# 33_DRAM-DDR4_2x16bit_96P.net
KiCad netlist of a schematic drawn in Altium Designer
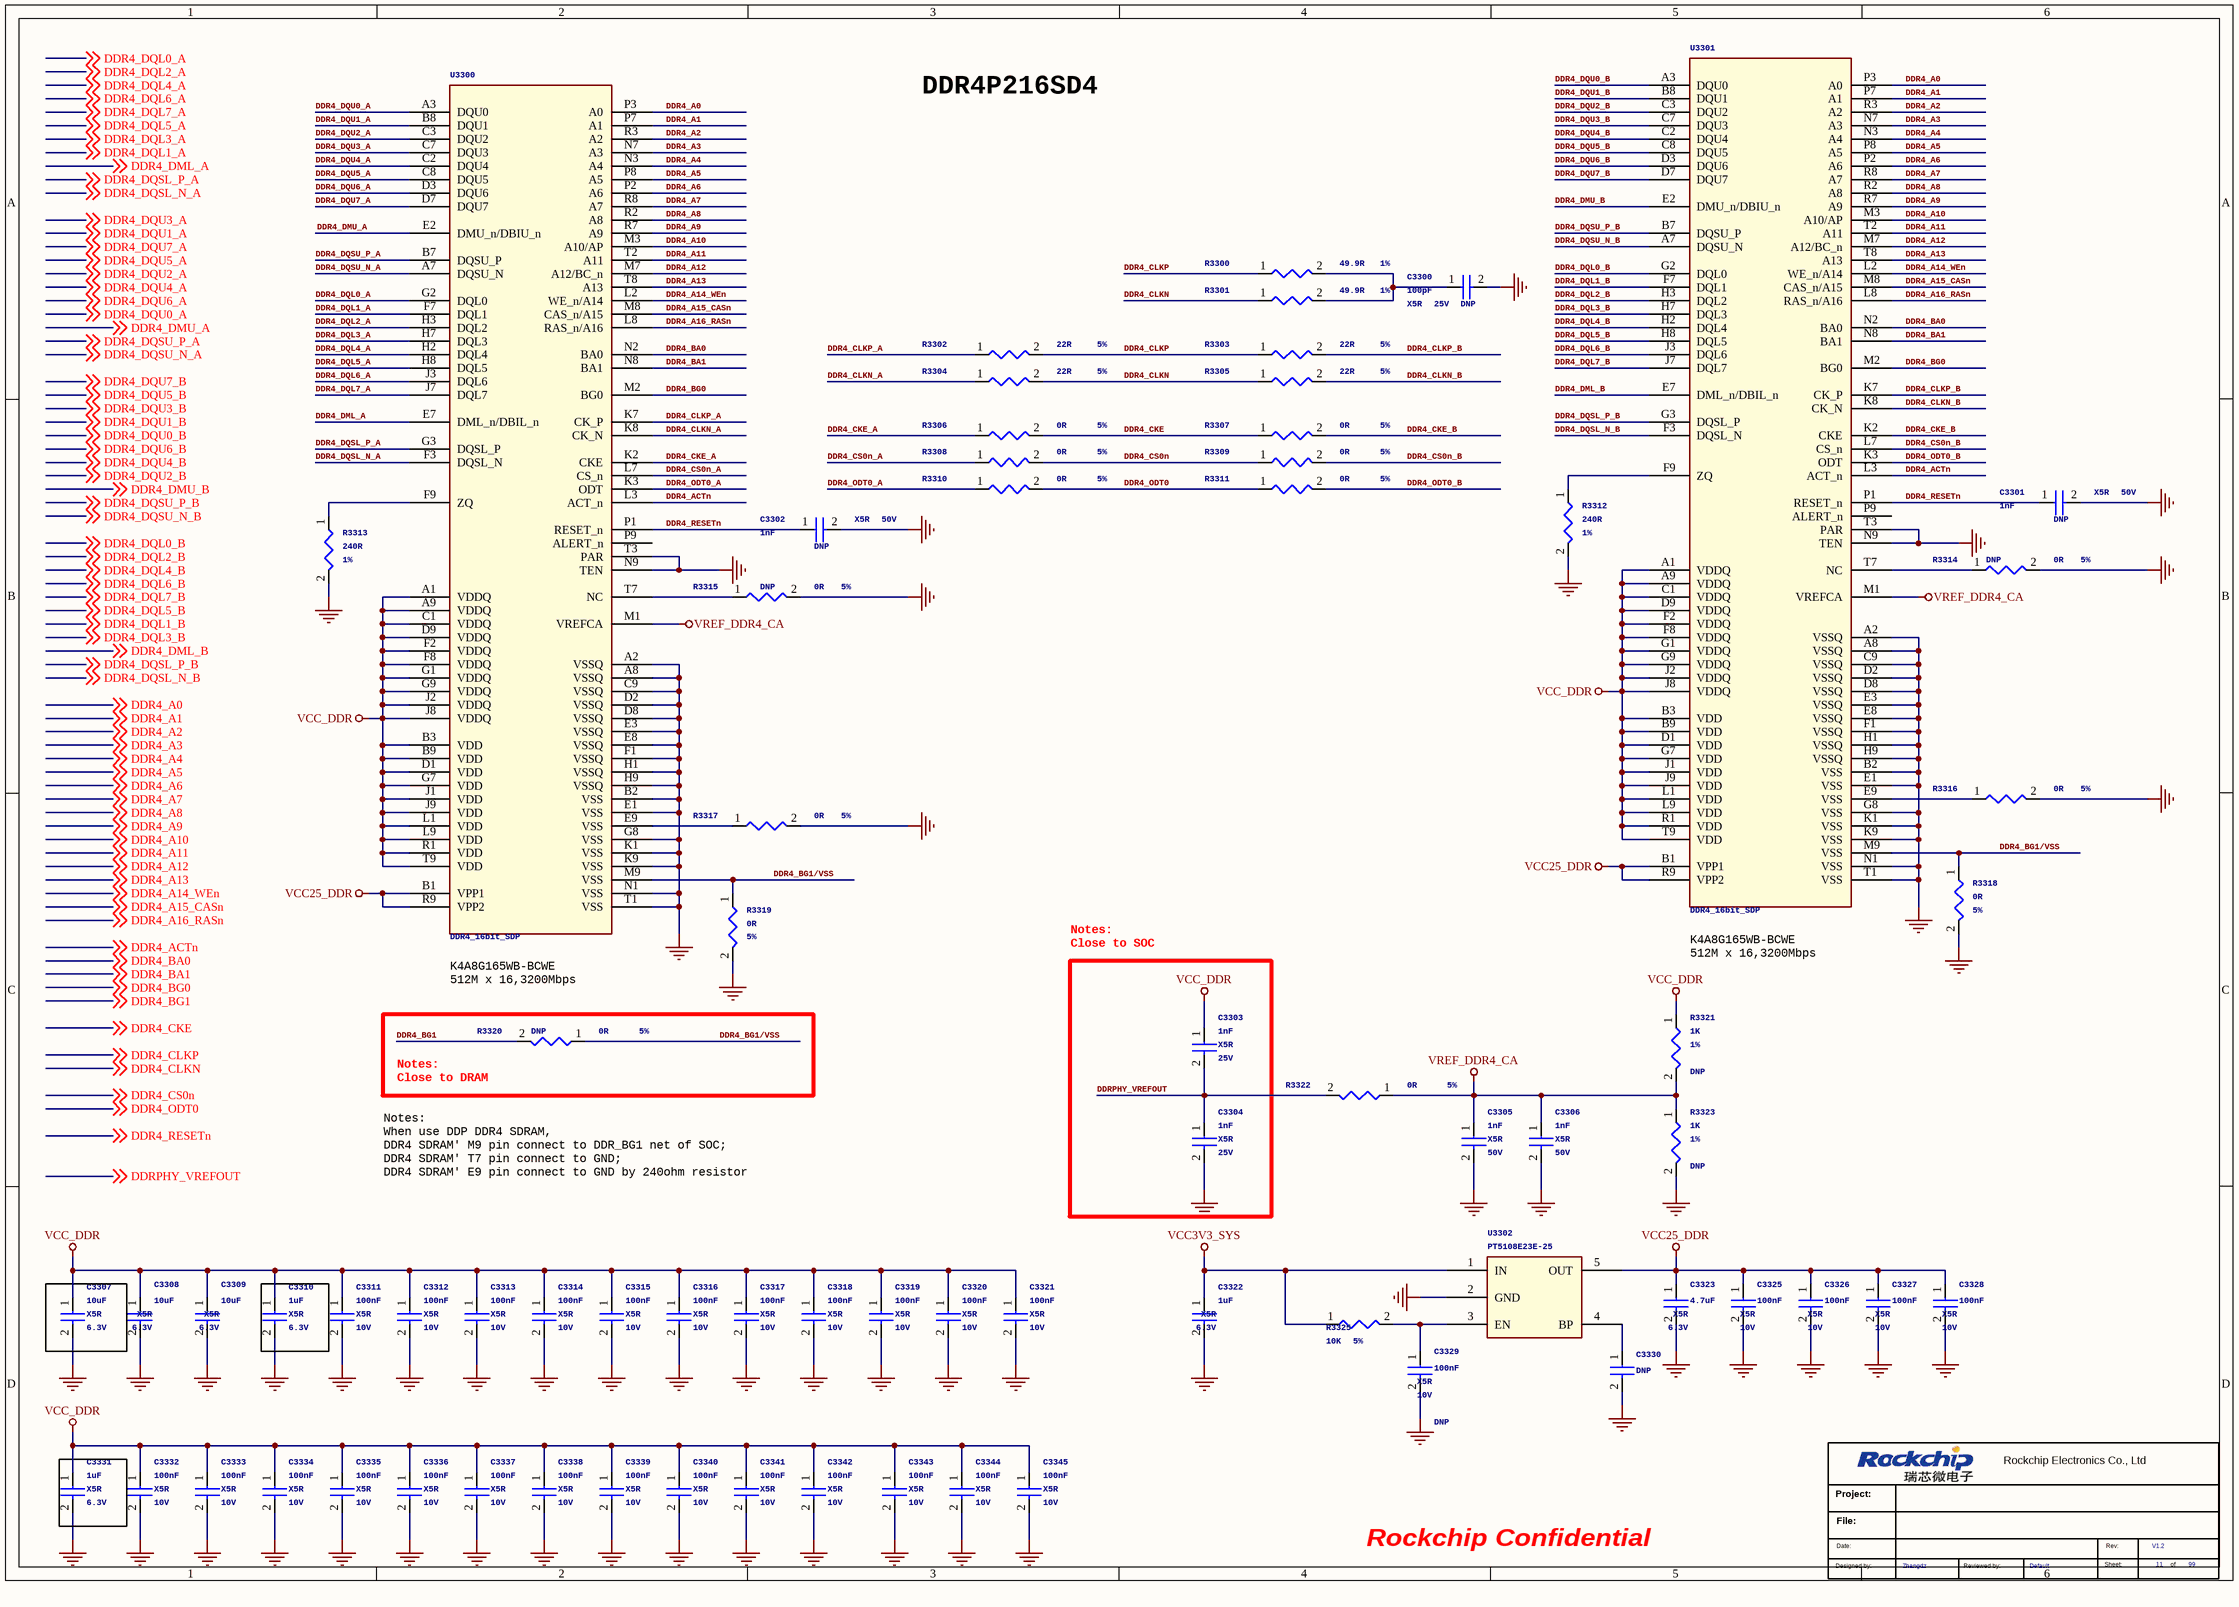
[diagram p0: 33.DRAM-DDR4_2x16bit_96P.SchDoc]

(export (version "E")
  (design (tool "Eeschema 10.0.6"))
  (components
    (comp (ref "*")
      (value "Rockchip_new")
      (fields
        (field (name "SCHEMATIC PAGE COUNT") "99")
        (field (name "SCHEMATIC PAGE NUMBER") "11")
        (field (name "DESIGNER") "Zhangdz")
        (field (name "REVISION") "V1.2")
        (field (name "CHECK") "Default")
      )
      (libsource (lib "*") (part "Rockchip_new"))
    )
    (comp (ref "C3300")
      (value "100pF")
      (footprint "C0201")
      (description "cap,100.00pF,+/-10%,25V,X5R,C0201")
      (fields
        (field (name "VOLTAGE") "25V")
        (field (name "DIELECTRIC") "X5R")
        (field (name "OPTION") "DNP")
        (field (name "MANUFACTURER") "TDK")
        (field (name "TOLERANCE") "10%")
        (field (name "CREATED BY") "JJJ")
      )
      (libsource (lib "*") (part "CAP NP"))
    )
    (comp (ref "C3301")
      (value "1nF")
      (footprint "C0402")
      (description "cap,1.00nF,+/-10%,50V,X5R,C0402")
      (fields
        (field (name "VOLTAGE") "50V")
        (field (name "DIELECTRIC") "X5R")
        (field (name "OPTION") "DNP")
        (field (name "MANUFACTURER") "TDK")
        (field (name "TOLERANCE") "10%")
        (field (name "CREATED BY") "JJJ")
      )
      (libsource (lib "*") (part "CAP NP"))
    )
    (comp (ref "C3302")
      (value "1nF")
      (footprint "C0402")
      (description "cap,1.00nF,+/-10%,50V,X5R,C0402")
      (fields
        (field (name "VOLTAGE") "50V")
        (field (name "DIELECTRIC") "X5R")
        (field (name "OPTION") "DNP")
        (field (name "MANUFACTURER") "TDK")
        (field (name "TOLERANCE") "10%")
        (field (name "CREATED BY") "JJJ")
      )
      (libsource (lib "*") (part "CAP NP"))
    )
    (comp (ref "C3303")
      (value "1nF")
      (footprint "C0201")
      (description "cap,1.00nF,+/-10%,25V,X5R,C0201")
      (fields
        (field (name "VOLTAGE") "25V")
        (field (name "DIELECTRIC") "X5R")
        (field (name "MANUFACTURER") "TDK")
        (field (name "TOLERANCE") "10%")
        (field (name "CREATED BY") "JJJ")
      )
      (libsource (lib "*") (part "CAP NP"))
    )
    (comp (ref "C3304")
      (value "1nF")
      (footprint "C0201")
      (description "cap,1.00nF,+/-10%,25V,X5R,C0201")
      (fields
        (field (name "VOLTAGE") "25V")
        (field (name "DIELECTRIC") "X5R")
        (field (name "TOLERANCE") "10%")
        (field (name "MANUFACTURER") "TDK")
        (field (name "CREATED BY") "JJJ")
      )
      (libsource (lib "*") (part "CAP NP"))
    )
    (comp (ref "C3305")
      (value "1nF")
      (footprint "C0402")
      (description "cap,1.00nF,+/-10%,50V,X5R,C0402")
      (fields
        (field (name "VOLTAGE") "50V")
        (field (name "DIELECTRIC") "X5R")
        (field (name "MANUFACTURER") "TDK")
        (field (name "TOLERANCE") "10%")
        (field (name "CREATED BY") "JJJ")
      )
      (libsource (lib "*") (part "CAP NP"))
    )
    (comp (ref "C3306")
      (value "1nF")
      (footprint "C0402")
      (description "cap,1.00nF,+/-10%,50V,X5R,C0402")
      (fields
        (field (name "VOLTAGE") "50V")
        (field (name "DIELECTRIC") "X5R")
        (field (name "TOLERANCE") "10%")
        (field (name "MANUFACTURER") "TDK")
        (field (name "CREATED BY") "JJJ")
      )
      (libsource (lib "*") (part "CAP NP"))
    )
    (comp (ref "C3307")
      (value "10uF")
      (footprint "C0603")
      (description "cap,10.00uF,+/-10%,6.3V,X5R,C0603")
      (fields
        (field (name "VOLTAGE") "6.3V")
        (field (name "DIELECTRIC") "X5R")
        (field (name "TOLERANCE") "10%")
        (field (name "MANUFACTURER") "TDK")
        (field (name "CREATED BY") "JJJ")
      )
      (libsource (lib "*") (part "CAP NP"))
    )
    (comp (ref "C3308")
      (value "10uF")
      (footprint "C0603")
      (description "cap,10.00uF,+/-10%,6.3V,X5R,C0603")
      (fields
        (field (name "VOLTAGE") "6.3V")
        (field (name "DIELECTRIC") "X5R")
        (field (name "TOLERANCE") "10%")
        (field (name "MANUFACTURER") "TDK")
        (field (name "CREATED BY") "JJJ")
      )
      (libsource (lib "*") (part "CAP NP"))
    )
    (comp (ref "C3309")
      (value "10uF")
      (footprint "C0603")
      (description "cap,10.00uF,+/-10%,6.3V,X5R,C0603")
      (fields
        (field (name "VOLTAGE") "6.3V")
        (field (name "DIELECTRIC") "X5R")
        (field (name "MANUFACTURER") "TDK")
        (field (name "TOLERANCE") "10%")
        (field (name "CREATED BY") "JJJ")
      )
      (libsource (lib "*") (part "CAP NP"))
    )
    (comp (ref "C3310")
      (value "1uF")
      (footprint "C0402")
      (description "cap,1.00uF,+/-10%,6.3V,X5R,C0402")
      (fields
        (field (name "VOLTAGE") "6.3V")
        (field (name "DIELECTRIC") "X5R")
        (field (name "TOLERANCE") "10%")
        (field (name "MANUFACTURER") "TDK")
        (field (name "CREATED BY") "JJJ")
      )
      (libsource (lib "*") (part "CAP NP"))
    )
    (comp (ref "C3311")
      (value "100nF")
      (footprint "C0402")
      (description "cap,100.00nF,+/-10%,10V,X5R,C0402")
      (fields
        (field (name "VOLTAGE") "10V")
        (field (name "DIELECTRIC") "X5R")
        (field (name "MANUFACTURER") "TDK")
        (field (name "TOLERANCE") "10%")
        (field (name "CREATED BY") "JJJ")
      )
      (libsource (lib "*") (part "CAP NP"))
    )
    (comp (ref "C3312")
      (value "100nF")
      (footprint "C0402")
      (description "cap,100.00nF,+/-10%,10V,X5R,C0402")
      (fields
        (field (name "VOLTAGE") "10V")
        (field (name "DIELECTRIC") "X5R")
        (field (name "TOLERANCE") "10%")
        (field (name "MANUFACTURER") "TDK")
        (field (name "CREATED BY") "JJJ")
      )
      (libsource (lib "*") (part "CAP NP"))
    )
    (comp (ref "C3313")
      (value "100nF")
      (footprint "C0402")
      (description "cap,100.00nF,+/-10%,10V,X5R,C0402")
      (fields
        (field (name "VOLTAGE") "10V")
        (field (name "DIELECTRIC") "X5R")
        (field (name "MANUFACTURER") "TDK")
        (field (name "TOLERANCE") "10%")
        (field (name "CREATED BY") "JJJ")
      )
      (libsource (lib "*") (part "CAP NP"))
    )
    (comp (ref "C3314")
      (value "100nF")
      (footprint "C0402")
      (description "cap,100.00nF,+/-10%,10V,X5R,C0402")
      (fields
        (field (name "VOLTAGE") "10V")
        (field (name "DIELECTRIC") "X5R")
        (field (name "MANUFACTURER") "TDK")
        (field (name "TOLERANCE") "10%")
        (field (name "CREATED BY") "JJJ")
      )
      (libsource (lib "*") (part "CAP NP"))
    )
    (comp (ref "C3315")
      (value "100nF")
      (footprint "C0402")
      (description "cap,100.00nF,+/-10%,10V,X5R,C0402")
      (fields
        (field (name "VOLTAGE") "10V")
        (field (name "DIELECTRIC") "X5R")
        (field (name "MANUFACTURER") "TDK")
        (field (name "TOLERANCE") "10%")
        (field (name "CREATED BY") "JJJ")
      )
      (libsource (lib "*") (part "CAP NP"))
    )
    (comp (ref "C3316")
      (value "100nF")
      (footprint "C0402")
      (description "cap,100.00nF,+/-10%,10V,X5R,C0402")
      (fields
        (field (name "VOLTAGE") "10V")
        (field (name "DIELECTRIC") "X5R")
        (field (name "TOLERANCE") "10%")
        (field (name "MANUFACTURER") "TDK")
        (field (name "CREATED BY") "JJJ")
      )
      (libsource (lib "*") (part "CAP NP"))
    )
    (comp (ref "C3317")
      (value "100nF")
      (footprint "C0402")
      (description "cap,100.00nF,+/-10%,10V,X5R,C0402")
      (fields
        (field (name "VOLTAGE") "10V")
        (field (name "DIELECTRIC") "X5R")
        (field (name "MANUFACTURER") "TDK")
        (field (name "TOLERANCE") "10%")
        (field (name "CREATED BY") "JJJ")
      )
      (libsource (lib "*") (part "CAP NP"))
    )
    (comp (ref "C3318")
      (value "100nF")
      (footprint "C0402")
      (description "cap,100.00nF,+/-10%,10V,X5R,C0402")
      (fields
        (field (name "VOLTAGE") "10V")
        (field (name "DIELECTRIC") "X5R")
        (field (name "TOLERANCE") "10%")
        (field (name "MANUFACTURER") "TDK")
        (field (name "CREATED BY") "JJJ")
      )
      (libsource (lib "*") (part "CAP NP"))
    )
    (comp (ref "C3319")
      (value "100nF")
      (footprint "C0402")
      (description "cap,100.00nF,+/-10%,10V,X5R,C0402")
      (fields
        (field (name "VOLTAGE") "10V")
        (field (name "DIELECTRIC") "X5R")
        (field (name "TOLERANCE") "10%")
        (field (name "MANUFACTURER") "TDK")
        (field (name "CREATED BY") "JJJ")
      )
      (libsource (lib "*") (part "CAP NP"))
    )
    (comp (ref "C3320")
      (value "100nF")
      (footprint "C0402")
      (description "cap,100.00nF,+/-10%,10V,X5R,C0402")
      (fields
        (field (name "VOLTAGE") "10V")
        (field (name "DIELECTRIC") "X5R")
        (field (name "MANUFACTURER") "TDK")
        (field (name "TOLERANCE") "10%")
        (field (name "CREATED BY") "JJJ")
      )
      (libsource (lib "*") (part "CAP NP"))
    )
    (comp (ref "C3321")
      (value "100nF")
      (footprint "C0402")
      (description "cap,100.00nF,+/-10%,10V,X5R,C0402")
      (fields
        (field (name "VOLTAGE") "10V")
        (field (name "DIELECTRIC") "X5R")
        (field (name "TOLERANCE") "10%")
        (field (name "MANUFACTURER") "TDK")
        (field (name "CREATED BY") "JJJ")
      )
      (libsource (lib "*") (part "CAP NP"))
    )
    (comp (ref "C3322")
      (value "1uF")
      (footprint "C0402")
      (description "cap,1.00uF,+/-10%,6.3V,X5R,C0402")
      (fields
        (field (name "VOLTAGE") "6.3V")
        (field (name "DIELECTRIC") "X5R")
        (field (name "MANUFACTURER") "TDK")
        (field (name "TOLERANCE") "10%")
        (field (name "CREATED BY") "JJJ")
      )
      (libsource (lib "*") (part "CAP NP"))
    )
    (comp (ref "C3323")
      (value "4.7uF")
      (footprint "C0402")
      (description "cap,4.70uF,+/-10%,6.3V,X5R,C0402")
      (fields
        (field (name "VOLTAGE") "6.3V")
        (field (name "DIELECTRIC") "X5R")
        (field (name "MANUFACTURER") "TDK")
        (field (name "TOLERANCE") "10%")
        (field (name "CREATED BY") "JJJ")
      )
      (libsource (lib "*") (part "CAP NP"))
    )
    (comp (ref "C3325")
      (value "100nF")
      (footprint "C0402")
      (description "cap,100.00nF,+/-10%,10V,X5R,C0402")
      (fields
        (field (name "VOLTAGE") "10V")
        (field (name "DIELECTRIC") "X5R")
        (field (name "TOLERANCE") "10%")
        (field (name "MANUFACTURER") "TDK")
        (field (name "CREATED BY") "JJJ")
      )
      (libsource (lib "*") (part "CAP NP"))
    )
    (comp (ref "C3326")
      (value "100nF")
      (footprint "C0402")
      (description "cap,100.00nF,+/-10%,10V,X5R,C0402")
      (fields
        (field (name "VOLTAGE") "10V")
        (field (name "DIELECTRIC") "X5R")
        (field (name "TOLERANCE") "10%")
        (field (name "MANUFACTURER") "TDK")
        (field (name "CREATED BY") "JJJ")
      )
      (libsource (lib "*") (part "CAP NP"))
    )
    (comp (ref "C3327")
      (value "100nF")
      (footprint "C0402")
      (description "cap,100.00nF,+/-10%,10V,X5R,C0402")
      (fields
        (field (name "VOLTAGE") "10V")
        (field (name "DIELECTRIC") "X5R")
        (field (name "MANUFACTURER") "TDK")
        (field (name "TOLERANCE") "10%")
        (field (name "CREATED BY") "JJJ")
      )
      (libsource (lib "*") (part "CAP NP"))
    )
    (comp (ref "C3328")
      (value "100nF")
      (footprint "C0402")
      (description "cap,100.00nF,+/-10%,10V,X5R,C0402")
      (fields
        (field (name "VOLTAGE") "10V")
        (field (name "DIELECTRIC") "X5R")
        (field (name "TOLERANCE") "10%")
        (field (name "MANUFACTURER") "TDK")
        (field (name "CREATED BY") "JJJ")
      )
      (libsource (lib "*") (part "CAP NP"))
    )
    (comp (ref "C3329")
      (value "100nF")
      (footprint "C0402")
      (description "cap,100.00nF,+/-10%,10V,X5R,C0402")
      (fields
        (field (name "VOLTAGE") "10V")
        (field (name "DIELECTRIC") "X5R")
        (field (name "MANUFACTURER") "TDK")
        (field (name "TOLERANCE") "10%")
        (field (name "OPTION") "DNP")
        (field (name "CREATED BY") "JJJ")
      )
      (libsource (lib "*") (part "CAP NP"))
    )
    (comp (ref "C3330")
      (value "DNP")
      (footprint "C0402")
      (description "Did Not Place.")
      (fields (field (name "CREATED BY") "JJJ"))
      (libsource (lib "*") (part "CAP NP"))
    )
    (comp (ref "C3331")
      (value "1uF")
      (footprint "C0402")
      (description "cap,1.00uF,+/-10%,6.3V,X5R,C0402")
      (fields
        (field (name "VOLTAGE") "6.3V")
        (field (name "DIELECTRIC") "X5R")
        (field (name "TOLERANCE") "10%")
        (field (name "MANUFACTURER") "TDK")
        (field (name "CREATED BY") "JJJ")
      )
      (libsource (lib "*") (part "CAP NP"))
    )
    (comp (ref "C3332")
      (value "100nF")
      (footprint "C0402")
      (description "cap,100.00nF,+/-10%,10V,X5R,C0402")
      (fields
        (field (name "VOLTAGE") "10V")
        (field (name "DIELECTRIC") "X5R")
        (field (name "TOLERANCE") "10%")
        (field (name "MANUFACTURER") "TDK")
        (field (name "CREATED BY") "JJJ")
      )
      (libsource (lib "*") (part "CAP NP"))
    )
    (comp (ref "C3333")
      (value "100nF")
      (footprint "C0402")
      (description "cap,100.00nF,+/-10%,10V,X5R,C0402")
      (fields
        (field (name "VOLTAGE") "10V")
        (field (name "DIELECTRIC") "X5R")
        (field (name "MANUFACTURER") "TDK")
        (field (name "TOLERANCE") "10%")
        (field (name "CREATED BY") "JJJ")
      )
      (libsource (lib "*") (part "CAP NP"))
    )
    (comp (ref "C3334")
      (value "100nF")
      (footprint "C0402")
      (description "cap,100.00nF,+/-10%,10V,X5R,C0402")
      (fields
        (field (name "VOLTAGE") "10V")
        (field (name "DIELECTRIC") "X5R")
        (field (name "MANUFACTURER") "TDK")
        (field (name "TOLERANCE") "10%")
        (field (name "CREATED BY") "JJJ")
      )
      (libsource (lib "*") (part "CAP NP"))
    )
    (comp (ref "C3335")
      (value "100nF")
      (footprint "C0402")
      (description "cap,100.00nF,+/-10%,10V,X5R,C0402")
      (fields
        (field (name "VOLTAGE") "10V")
        (field (name "DIELECTRIC") "X5R")
        (field (name "TOLERANCE") "10%")
        (field (name "MANUFACTURER") "TDK")
        (field (name "CREATED BY") "JJJ")
      )
      (libsource (lib "*") (part "CAP NP"))
    )
    (comp (ref "C3336")
      (value "100nF")
      (footprint "C0402")
      (description "cap,100.00nF,+/-10%,10V,X5R,C0402")
      (fields
        (field (name "VOLTAGE") "10V")
        (field (name "DIELECTRIC") "X5R")
        (field (name "MANUFACTURER") "TDK")
        (field (name "TOLERANCE") "10%")
        (field (name "CREATED BY") "JJJ")
      )
      (libsource (lib "*") (part "CAP NP"))
    )
    (comp (ref "C3337")
      (value "100nF")
      (footprint "C0402")
      (description "cap,100.00nF,+/-10%,10V,X5R,C0402")
      (fields
        (field (name "VOLTAGE") "10V")
        (field (name "DIELECTRIC") "X5R")
        (field (name "TOLERANCE") "10%")
        (field (name "MANUFACTURER") "TDK")
        (field (name "CREATED BY") "JJJ")
      )
      (libsource (lib "*") (part "CAP NP"))
    )
    (comp (ref "C3338")
      (value "100nF")
      (footprint "C0402")
      (description "cap,100.00nF,+/-10%,10V,X5R,C0402")
      (fields
        (field (name "VOLTAGE") "10V")
        (field (name "DIELECTRIC") "X5R")
        (field (name "TOLERANCE") "10%")
        (field (name "MANUFACTURER") "TDK")
        (field (name "CREATED BY") "JJJ")
      )
      (libsource (lib "*") (part "CAP NP"))
    )
    (comp (ref "C3339")
      (value "100nF")
      (footprint "C0402")
      (description "cap,100.00nF,+/-10%,10V,X5R,C0402")
      (fields
        (field (name "VOLTAGE") "10V")
        (field (name "DIELECTRIC") "X5R")
        (field (name "MANUFACTURER") "TDK")
        (field (name "TOLERANCE") "10%")
        (field (name "CREATED BY") "JJJ")
      )
      (libsource (lib "*") (part "CAP NP"))
    )
    (comp (ref "C3340")
      (value "100nF")
      (footprint "C0402")
      (description "cap,100.00nF,+/-10%,10V,X5R,C0402")
      (fields
        (field (name "VOLTAGE") "10V")
        (field (name "DIELECTRIC") "X5R")
        (field (name "TOLERANCE") "10%")
        (field (name "MANUFACTURER") "TDK")
        (field (name "CREATED BY") "JJJ")
      )
      (libsource (lib "*") (part "CAP NP"))
    )
    (comp (ref "C3341")
      (value "100nF")
      (footprint "C0402")
      (description "cap,100.00nF,+/-10%,10V,X5R,C0402")
      (fields
        (field (name "VOLTAGE") "10V")
        (field (name "DIELECTRIC") "X5R")
        (field (name "MANUFACTURER") "TDK")
        (field (name "TOLERANCE") "10%")
        (field (name "CREATED BY") "JJJ")
      )
      (libsource (lib "*") (part "CAP NP"))
    )
    (comp (ref "C3342")
      (value "100nF")
      (footprint "C0402")
      (description "cap,100.00nF,+/-10%,10V,X5R,C0402")
      (fields
        (field (name "VOLTAGE") "10V")
        (field (name "DIELECTRIC") "X5R")
        (field (name "TOLERANCE") "10%")
        (field (name "MANUFACTURER") "TDK")
        (field (name "CREATED BY") "JJJ")
      )
      (libsource (lib "*") (part "CAP NP"))
    )
    (comp (ref "C3343")
      (value "100nF")
      (footprint "C0402")
      (description "cap,100.00nF,+/-10%,10V,X5R,C0402")
      (fields
        (field (name "VOLTAGE") "10V")
        (field (name "DIELECTRIC") "X5R")
        (field (name "MANUFACTURER") "TDK")
        (field (name "TOLERANCE") "10%")
        (field (name "CREATED BY") "JJJ")
      )
      (libsource (lib "*") (part "CAP NP"))
    )
    (comp (ref "C3344")
      (value "100nF")
      (footprint "C0402")
      (description "cap,100.00nF,+/-10%,10V,X5R,C0402")
      (fields
        (field (name "VOLTAGE") "10V")
        (field (name "DIELECTRIC") "X5R")
        (field (name "MANUFACTURER") "TDK")
        (field (name "TOLERANCE") "10%")
        (field (name "CREATED BY") "JJJ")
      )
      (libsource (lib "*") (part "CAP NP"))
    )
    (comp (ref "C3345")
      (value "100nF")
      (footprint "C0402")
      (description "cap,100.00nF,+/-10%,10V,X5R,C0402")
      (fields
        (field (name "VOLTAGE") "10V")
        (field (name "DIELECTRIC") "X5R")
        (field (name "TOLERANCE") "10%")
        (field (name "MANUFACTURER") "TDK")
        (field (name "CREATED BY") "JJJ")
      )
      (libsource (lib "*") (part "CAP NP"))
    )
    (comp (ref "R3300")
      (value "49.9R")
      (footprint "R0201")
      (description "通用厚膜电阻,49R9,+/-1%,R0201,1/20W.")
      (fields
        (field (name "TOLERANCE") "1%")
        (field (name "MANUFACTURER") "YAGEO")
        (field (name "CREATED BY") "YTL")
      )
      (libsource (lib "*") (part "RESISTOR"))
    )
    (comp (ref "R3301")
      (value "49.9R")
      (footprint "R0201")
      (description "通用厚膜电阻,49R9,+/-1%,R0201,1/20W.")
      (fields
        (field (name "TOLERANCE") "1%")
        (field (name "MANUFACTURER") "YAGEO")
        (field (name "CREATED BY") "YTL")
      )
      (libsource (lib "*") (part "RESISTOR"))
    )
    (comp (ref "R3302")
      (value "22R")
      (footprint "R0201")
      (description "通用厚膜电阻,22R,+/-5%,R0201,1/20W.")
      (fields
        (field (name "TOLERANCE") "5%")
        (field (name "MANUFACTURER") "YAGEO")
        (field (name "CREATED BY") "YTL")
      )
      (libsource (lib "*") (part "RESISTOR"))
    )
    (comp (ref "R3303")
      (value "22R")
      (footprint "R0201")
      (description "通用厚膜电阻,22R,+/-5%,R0201,1/20W.")
      (fields
        (field (name "TOLERANCE") "5%")
        (field (name "MANUFACTURER") "YAGEO")
        (field (name "CREATED BY") "YTL")
      )
      (libsource (lib "*") (part "RESISTOR"))
    )
    (comp (ref "R3304")
      (value "22R")
      (footprint "R0201")
      (description "通用厚膜电阻,22R,+/-5%,R0201,1/20W.")
      (fields
        (field (name "TOLERANCE") "5%")
        (field (name "MANUFACTURER") "YAGEO")
        (field (name "CREATED BY") "YTL")
      )
      (libsource (lib "*") (part "RESISTOR"))
    )
    (comp (ref "R3305")
      (value "22R")
      (footprint "R0201")
      (description "通用厚膜电阻,22R,+/-5%,R0201,1/20W.")
      (fields
        (field (name "TOLERANCE") "5%")
        (field (name "MANUFACTURER") "YAGEO")
        (field (name "CREATED BY") "YTL")
      )
      (libsource (lib "*") (part "RESISTOR"))
    )
    (comp (ref "R3306")
      (value "0R")
      (footprint "R0201")
      (description "通用厚膜电阻,0R,+/-5%,R0201,1/20W.")
      (fields
        (field (name "TOLERANCE") "5%")
        (field (name "MANUFACTURER") "YAGEO")
        (field (name "CREATED BY") "YTL")
      )
      (libsource (lib "*") (part "RESISTOR"))
    )
    (comp (ref "R3307")
      (value "0R")
      (footprint "R0201")
      (description "通用厚膜电阻,0R,+/-5%,R0201,1/20W.")
      (fields
        (field (name "TOLERANCE") "5%")
        (field (name "MANUFACTURER") "YAGEO")
        (field (name "CREATED BY") "YTL")
      )
      (libsource (lib "*") (part "RESISTOR"))
    )
    (comp (ref "R3308")
      (value "0R")
      (footprint "R0201")
      (description "通用厚膜电阻,0R,+/-5%,R0201,1/20W.")
      (fields
        (field (name "TOLERANCE") "5%")
        (field (name "MANUFACTURER") "YAGEO")
        (field (name "CREATED BY") "YTL")
      )
      (libsource (lib "*") (part "RESISTOR"))
    )
    (comp (ref "R3309")
      (value "0R")
      (footprint "R0201")
      (description "通用厚膜电阻,0R,+/-5%,R0201,1/20W.")
      (fields
        (field (name "TOLERANCE") "5%")
        (field (name "MANUFACTURER") "YAGEO")
        (field (name "CREATED BY") "YTL")
      )
      (libsource (lib "*") (part "RESISTOR"))
    )
    (comp (ref "R3310")
      (value "0R")
      (footprint "R0201")
      (description "通用厚膜电阻,0R,+/-5%,R0201,1/20W.")
      (fields
        (field (name "TOLERANCE") "5%")
        (field (name "MANUFACTURER") "YAGEO")
        (field (name "CREATED BY") "YTL")
      )
      (libsource (lib "*") (part "RESISTOR"))
    )
    (comp (ref "R3311")
      (value "0R")
      (footprint "R0201")
      (description "通用厚膜电阻,0R,+/-5%,R0201,1/20W.")
      (fields
        (field (name "TOLERANCE") "5%")
        (field (name "MANUFACTURER") "YAGEO")
        (field (name "CREATED BY") "YTL")
      )
      (libsource (lib "*") (part "RESISTOR"))
    )
    (comp (ref "R3312")
      (value "240R")
      (footprint "R0402")
      (description "通用厚膜电阻,240R,+/-1%,R0402,1/16W.")
      (fields
        (field (name "TOLERANCE") "1%")
        (field (name "MANUFACTURER") "YAGEO")
        (field (name "CREATED BY") "YTL")
      )
      (libsource (lib "*") (part "RESISTOR"))
    )
    (comp (ref "R3313")
      (value "240R")
      (footprint "R0402")
      (description "通用厚膜电阻,240R,+/-1%,R0402,1/16W.")
      (fields
        (field (name "TOLERANCE") "1%")
        (field (name "MANUFACTURER") "YAGEO")
        (field (name "CREATED BY") "YTL")
      )
      (libsource (lib "*") (part "RESISTOR"))
    )
    (comp (ref "R3314")
      (value "0R")
      (footprint "R0402")
      (description "通用厚膜电阻,0R,+/-5%,R0402,1/16W.")
      (fields
        (field (name "TOLERANCE") "5%")
        (field (name "OPTION") "DNP")
        (field (name "MANUFACTURER") "YAGEO")
        (field (name "CREATED BY") "YTL")
      )
      (libsource (lib "*") (part "RESISTOR"))
    )
    (comp (ref "R3315")
      (value "0R")
      (footprint "R0402")
      (description "通用厚膜电阻,0R,+/-5%,R0402,1/16W.")
      (fields
        (field (name "TOLERANCE") "5%")
        (field (name "MANUFACTURER") "YAGEO")
        (field (name "OPTION") "DNP")
        (field (name "CREATED BY") "YTL")
      )
      (libsource (lib "*") (part "RESISTOR"))
    )
    (comp (ref "R3316")
      (value "0R")
      (footprint "R0402")
      (description "通用厚膜电阻,0R,+/-5%,R0402,1/16W.")
      (fields
        (field (name "TOLERANCE") "5%")
        (field (name "MANUFACTURER") "YAGEO")
        (field (name "CREATED BY") "YTL")
      )
      (libsource (lib "*") (part "RESISTOR"))
    )
    (comp (ref "R3317")
      (value "0R")
      (footprint "R0402")
      (description "通用厚膜电阻,0R,+/-5%,R0402,1/16W.")
      (fields
        (field (name "TOLERANCE") "5%")
        (field (name "MANUFACTURER") "YAGEO")
        (field (name "CREATED BY") "YTL")
      )
      (libsource (lib "*") (part "RESISTOR"))
    )
    (comp (ref "R3318")
      (value "0R")
      (footprint "R0402")
      (description "通用厚膜电阻,0R,+/-5%,R0402,1/16W.")
      (fields
        (field (name "TOLERANCE") "5%")
        (field (name "MANUFACTURER") "YAGEO")
        (field (name "CREATED BY") "YTL")
      )
      (libsource (lib "*") (part "RESISTOR"))
    )
    (comp (ref "R3319")
      (value "0R")
      (footprint "R0402")
      (description "通用厚膜电阻,0R,+/-5%,R0402,1/16W.")
      (fields
        (field (name "TOLERANCE") "5%")
        (field (name "MANUFACTURER") "YAGEO")
        (field (name "CREATED BY") "YTL")
      )
      (libsource (lib "*") (part "RESISTOR"))
    )
    (comp (ref "R3320")
      (value "0R")
      (footprint "R0402")
      (description "通用厚膜电阻,0R,+/-5%,R0402,1/16W.")
      (fields
        (field (name "TOLERANCE") "5%")
        (field (name "MANUFACTURER") "YAGEO")
        (field (name "OPTION") "DNP")
        (field (name "CREATED BY") "YTL")
      )
      (libsource (lib "*") (part "RESISTOR"))
    )
    (comp (ref "R3321")
      (value "1K")
      (footprint "R0402")
      (description "通用厚膜电阻,1K,+/-1%,R0402,1/16W.")
      (fields
        (field (name "TOLERANCE") "1%")
        (field (name "MANUFACTURER") "YAGEO")
        (field (name "OPTION") "DNP")
        (field (name "CREATED BY") "YTL")
      )
      (libsource (lib "*") (part "RESISTOR"))
    )
    (comp (ref "R3322")
      (value "0R")
      (footprint "R0402")
      (description "通用厚膜电阻,0R,+/-5%,R0402,1/16W.")
      (fields
        (field (name "TOLERANCE") "5%")
        (field (name "MANUFACTURER") "YAGEO")
        (field (name "CREATED BY") "YTL")
      )
      (libsource (lib "*") (part "RESISTOR"))
    )
    (comp (ref "R3323")
      (value "1K")
      (footprint "R0402")
      (description "通用厚膜电阻,1K,+/-1%,R0402,1/16W.")
      (fields
        (field (name "TOLERANCE") "1%")
        (field (name "MANUFACTURER") "YAGEO")
        (field (name "OPTION") "DNP")
        (field (name "CREATED BY") "YTL")
      )
      (libsource (lib "*") (part "RESISTOR"))
    )
    (comp (ref "R3325")
      (value "10K")
      (footprint "R0402")
      (description "通用厚膜电阻,10K,+/-5%,R0402,1/16W.")
      (fields
        (field (name "TOLERANCE") "5%")
        (field (name "MANUFACTURER") "YAGEO")
        (field (name "CREATED BY") "YTL")
      )
      (libsource (lib "*") (part "RESISTOR"))
    )
    (comp (ref "U3300")
      (value "DDR4_16bit_SDP")
      (footprint "FBGA96_14R00X11R00X1R20")
      (description "DDR4，16bit,96ball FBGA")
      (fields (field (name "MANUFACTURER") "DRAM") (field (name "CREATED BY") "JJJ"))
      (libsource (lib "*") (part "DDR4_16bit"))
    )
    (comp (ref "U3301")
      (value "DDR4_16bit_SDP")
      (footprint "FBGA96_14R00X11R00X1R20")
      (description "DDR4，16bit,96ball FBGA")
      (fields (field (name "MANUFACTURER") "DRAM") (field (name "CREATED BY") "JJJ"))
      (libsource (lib "*") (part "DDR4_16bit"))
    )
    (comp (ref "U3302")
      (value "PT5108E23E-25")
      (footprint "SOT_23_5")
      (description "High-PSRR 500mA LDO.Output2.5V.")
      (fields (field (name "MANUFACTURER") "Powtech（华润矽威）") (field (name "CREATED BY") "JJJ"))
      (libsource (lib "*") (part "LDO_PT5108"))
    )
  )
  (nets
    (net (code "1") (name "/DDR4_BG1{slash}VSS") (class "Default")
      (node (ref "R3318") (pin "1") (pinfunction "1_1") (pintype "passive"))
      (node (ref "R3319") (pin "1") (pinfunction "1_1") (pintype "passive"))
      (node (ref "R3320") (pin "1") (pinfunction "1_1") (pintype "passive"))
      (node (ref "U3300") (pin "M9") (pinfunction "VSS_M9") (pintype "power_in"))
      (node (ref "U3301") (pin "M9") (pinfunction "VSS_M9") (pintype "power_in"))
    )
    (net (code "2") (name "/DDR4_CKE_A") (class "Default")
      (node (ref "R3306") (pin "1") (pinfunction "1_1") (pintype "passive"))
      (node (ref "U3300") (pin "K2") (pinfunction "CKE_K2") (pintype "passive"))
    )
    (net (code "3") (name "/DDR4_CKE_B") (class "Default")
      (node (ref "R3307") (pin "2") (pinfunction "2_2") (pintype "passive"))
      (node (ref "U3301") (pin "K2") (pinfunction "CKE_K2") (pintype "passive"))
    )
    (net (code "4") (name "/DDR4_CLKN_A") (class "Default")
      (node (ref "R3304") (pin "1") (pinfunction "1_1") (pintype "passive"))
      (node (ref "U3300") (pin "K8") (pinfunction "CK_N_K8") (pintype "passive"))
    )
    (net (code "5") (name "/DDR4_CLKN_B") (class "Default")
      (node (ref "R3305") (pin "2") (pinfunction "2_2") (pintype "passive"))
      (node (ref "U3301") (pin "K8") (pinfunction "CK_N_K8") (pintype "passive"))
    )
    (net (code "6") (name "/DDR4_CLKP_A") (class "Default")
      (node (ref "R3302") (pin "1") (pinfunction "1_1") (pintype "passive"))
      (node (ref "U3300") (pin "K7") (pinfunction "CK_P_K7") (pintype "passive"))
    )
    (net (code "7") (name "/DDR4_CLKP_B") (class "Default")
      (node (ref "R3303") (pin "2") (pinfunction "2_2") (pintype "passive"))
      (node (ref "U3301") (pin "K7") (pinfunction "CK_P_K7") (pintype "passive"))
    )
    (net (code "8") (name "/DDR4_CS0n_A") (class "Default")
      (node (ref "R3308") (pin "1") (pinfunction "1_1") (pintype "passive"))
      (node (ref "U3300") (pin "L7") (pinfunction "CS_n_L7") (pintype "passive"))
    )
    (net (code "9") (name "/DDR4_CS0n_B") (class "Default")
      (node (ref "R3309") (pin "2") (pinfunction "2_2") (pintype "passive"))
      (node (ref "U3301") (pin "L7") (pinfunction "CS_n_L7") (pintype "passive"))
    )
    (net (code "10") (name "/DDR4_ODT0_A") (class "Default")
      (node (ref "R3310") (pin "1") (pinfunction "1_1") (pintype "passive"))
      (node (ref "U3300") (pin "K3") (pinfunction "ODT_K3") (pintype "passive"))
    )
    (net (code "11") (name "/DDR4_ODT0_B") (class "Default")
      (node (ref "R3311") (pin "2") (pinfunction "2_2") (pintype "passive"))
      (node (ref "U3301") (pin "K3") (pinfunction "ODT_K3") (pintype "passive"))
    )
    (net (code "12") (name "DDR4_A0") (class "Default")
      (node (ref "U3300") (pin "P3") (pinfunction "A0_P3") (pintype "passive"))
      (node (ref "U3301") (pin "P3") (pinfunction "A0_P3") (pintype "passive"))
    )
    (net (code "13") (name "DDR4_A1") (class "Default")
      (node (ref "U3300") (pin "P7") (pinfunction "A1_P7") (pintype "passive"))
      (node (ref "U3301") (pin "P7") (pinfunction "A1_P7") (pintype "passive"))
    )
    (net (code "14") (name "DDR4_A2") (class "Default")
      (node (ref "U3300") (pin "R3") (pinfunction "A2_R3") (pintype "passive"))
      (node (ref "U3301") (pin "R3") (pinfunction "A2_R3") (pintype "passive"))
    )
    (net (code "15") (name "DDR4_A3") (class "Default")
      (node (ref "U3300") (pin "N7") (pinfunction "A3_N7") (pintype "passive"))
      (node (ref "U3301") (pin "N7") (pinfunction "A3_N7") (pintype "passive"))
    )
    (net (code "16") (name "DDR4_A4") (class "Default")
      (node (ref "U3300") (pin "N3") (pinfunction "A4_N3") (pintype "passive"))
      (node (ref "U3301") (pin "N3") (pinfunction "A4_N3") (pintype "passive"))
    )
    (net (code "17") (name "DDR4_A5") (class "Default")
      (node (ref "U3300") (pin "P8") (pinfunction "A5_P8") (pintype "passive"))
      (node (ref "U3301") (pin "P8") (pinfunction "A5_P8") (pintype "passive"))
    )
    (net (code "18") (name "DDR4_A6") (class "Default")
      (node (ref "U3300") (pin "P2") (pinfunction "A6_P2") (pintype "passive"))
      (node (ref "U3301") (pin "P2") (pinfunction "A6_P2") (pintype "passive"))
    )
    (net (code "19") (name "DDR4_A7") (class "Default")
      (node (ref "U3300") (pin "R8") (pinfunction "A7_R8") (pintype "passive"))
      (node (ref "U3301") (pin "R8") (pinfunction "A7_R8") (pintype "passive"))
    )
    (net (code "20") (name "DDR4_A8") (class "Default")
      (node (ref "U3300") (pin "R2") (pinfunction "A8_R2") (pintype "passive"))
      (node (ref "U3301") (pin "R2") (pinfunction "A8_R2") (pintype "passive"))
    )
    (net (code "21") (name "DDR4_A9") (class "Default")
      (node (ref "U3300") (pin "R7") (pinfunction "A9_R7") (pintype "passive"))
      (node (ref "U3301") (pin "R7") (pinfunction "A9_R7") (pintype "passive"))
    )
    (net (code "22") (name "DDR4_A10") (class "Default")
      (node (ref "U3300") (pin "M3") (pinfunction "A10/AP_M3") (pintype "passive"))
      (node (ref "U3301") (pin "M3") (pinfunction "A10/AP_M3") (pintype "passive"))
    )
    (net (code "23") (name "DDR4_A11") (class "Default")
      (node (ref "U3300") (pin "T2") (pinfunction "A11_T2") (pintype "passive"))
      (node (ref "U3301") (pin "T2") (pinfunction "A11_T2") (pintype "passive"))
    )
    (net (code "24") (name "DDR4_A12") (class "Default")
      (node (ref "U3300") (pin "M7") (pinfunction "A12/BC_n_M7") (pintype "passive"))
      (node (ref "U3301") (pin "M7") (pinfunction "A12/BC_n_M7") (pintype "passive"))
    )
    (net (code "25") (name "DDR4_A13") (class "Default")
      (node (ref "U3300") (pin "T8") (pinfunction "A13_T8") (pintype "passive"))
      (node (ref "U3301") (pin "T8") (pinfunction "A13_T8") (pintype "passive"))
    )
    (net (code "26") (name "DDR4_A14_WEn") (class "Default")
      (node (ref "U3300") (pin "L2") (pinfunction "WE_n/A14_L2") (pintype "passive"))
      (node (ref "U3301") (pin "L2") (pinfunction "WE_n/A14_L2") (pintype "passive"))
    )
    (net (code "27") (name "DDR4_A15_CASn") (class "Default")
      (node (ref "U3300") (pin "M8") (pinfunction "CAS_n/A15_M8") (pintype "passive"))
      (node (ref "U3301") (pin "M8") (pinfunction "CAS_n/A15_M8") (pintype "passive"))
    )
    (net (code "28") (name "DDR4_A16_RASn") (class "Default")
      (node (ref "U3300") (pin "L8") (pinfunction "RAS_n/A16_L8") (pintype "passive"))
      (node (ref "U3301") (pin "L8") (pinfunction "RAS_n/A16_L8") (pintype "passive"))
    )
    (net (code "29") (name "DDR4_ACTn") (class "Default")
      (node (ref "U3300") (pin "L3") (pinfunction "ACT_n_L3") (pintype "passive"))
      (node (ref "U3301") (pin "L3") (pinfunction "ACT_n_L3") (pintype "passive"))
    )
    (net (code "30") (name "DDR4_BA0") (class "Default")
      (node (ref "U3300") (pin "N2") (pinfunction "BA0_N2") (pintype "passive"))
      (node (ref "U3301") (pin "N2") (pinfunction "BA0_N2") (pintype "passive"))
    )
    (net (code "31") (name "DDR4_BA1") (class "Default")
      (node (ref "U3300") (pin "N8") (pinfunction "BA1_N8") (pintype "passive"))
      (node (ref "U3301") (pin "N8") (pinfunction "BA1_N8") (pintype "passive"))
    )
    (net (code "32") (name "DDR4_BG0") (class "Default")
      (node (ref "U3300") (pin "M2") (pinfunction "BG0_M2") (pintype "passive"))
      (node (ref "U3301") (pin "M2") (pinfunction "BG0_M2") (pintype "passive"))
    )
    (net (code "33") (name "DDR4_BG1") (class "Default")
      (node (ref "R3320") (pin "2") (pinfunction "2_2") (pintype "passive"))
    )
    (net (code "34") (name "DDR4_CKE") (class "Default")
      (node (ref "R3306") (pin "2") (pinfunction "2_2") (pintype "passive"))
      (node (ref "R3307") (pin "1") (pinfunction "1_1") (pintype "passive"))
    )
    (net (code "35") (name "DDR4_CLKN") (class "Default")
      (node (ref "R3301") (pin "1") (pinfunction "1_1") (pintype "passive"))
      (node (ref "R3304") (pin "2") (pinfunction "2_2") (pintype "passive"))
      (node (ref "R3305") (pin "1") (pinfunction "1_1") (pintype "passive"))
    )
    (net (code "36") (name "DDR4_CLKP") (class "Default")
      (node (ref "R3300") (pin "1") (pinfunction "1_1") (pintype "passive"))
      (node (ref "R3302") (pin "2") (pinfunction "2_2") (pintype "passive"))
      (node (ref "R3303") (pin "1") (pinfunction "1_1") (pintype "passive"))
    )
    (net (code "37") (name "DDR4_CS0n") (class "Default")
      (node (ref "R3308") (pin "2") (pinfunction "2_2") (pintype "passive"))
      (node (ref "R3309") (pin "1") (pinfunction "1_1") (pintype "passive"))
    )
    (net (code "38") (name "DDR4_DML_A") (class "Default")
      (node (ref "U3300") (pin "E7") (pinfunction "DML_n/DBIL_n_E7") (pintype "passive"))
    )
    (net (code "39") (name "DDR4_DML_B") (class "Default")
      (node (ref "U3301") (pin "E7") (pinfunction "DML_n/DBIL_n_E7") (pintype "passive"))
    )
    (net (code "40") (name "DDR4_DMU_A") (class "Default")
      (node (ref "U3300") (pin "E2") (pinfunction "DMU_n/DBIU_n_E2") (pintype "passive"))
    )
    (net (code "41") (name "DDR4_DMU_B") (class "Default")
      (node (ref "U3301") (pin "E2") (pinfunction "DMU_n/DBIU_n_E2") (pintype "passive"))
    )
    (net (code "42") (name "DDR4_DQL0_A") (class "Default")
      (node (ref "U3300") (pin "G2") (pinfunction "DQL0_G2") (pintype "passive"))
    )
    (net (code "43") (name "DDR4_DQL0_B") (class "Default")
      (node (ref "U3301") (pin "G2") (pinfunction "DQL0_G2") (pintype "passive"))
    )
    (net (code "44") (name "DDR4_DQL1_A") (class "Default")
      (node (ref "U3300") (pin "F7") (pinfunction "DQL1_F7") (pintype "passive"))
    )
    (net (code "45") (name "DDR4_DQL1_B") (class "Default")
      (node (ref "U3301") (pin "F7") (pinfunction "DQL1_F7") (pintype "passive"))
    )
    (net (code "46") (name "DDR4_DQL2_A") (class "Default")
      (node (ref "U3300") (pin "H3") (pinfunction "DQL2_H3") (pintype "passive"))
    )
    (net (code "47") (name "DDR4_DQL2_B") (class "Default")
      (node (ref "U3301") (pin "H3") (pinfunction "DQL2_H3") (pintype "passive"))
    )
    (net (code "48") (name "DDR4_DQL3_A") (class "Default")
      (node (ref "U3300") (pin "H7") (pinfunction "DQL3_H7") (pintype "passive"))
    )
    (net (code "49") (name "DDR4_DQL3_B") (class "Default")
      (node (ref "U3301") (pin "H7") (pinfunction "DQL3_H7") (pintype "passive"))
    )
    (net (code "50") (name "DDR4_DQL4_A") (class "Default")
      (node (ref "U3300") (pin "H2") (pinfunction "DQL4_H2") (pintype "passive"))
    )
    (net (code "51") (name "DDR4_DQL4_B") (class "Default")
      (node (ref "U3301") (pin "H2") (pinfunction "DQL4_H2") (pintype "passive"))
    )
    (net (code "52") (name "DDR4_DQL5_A") (class "Default")
      (node (ref "U3300") (pin "H8") (pinfunction "DQL5_H8") (pintype "passive"))
    )
    (net (code "53") (name "DDR4_DQL5_B") (class "Default")
      (node (ref "U3301") (pin "H8") (pinfunction "DQL5_H8") (pintype "passive"))
    )
    (net (code "54") (name "DDR4_DQL6_A") (class "Default")
      (node (ref "U3300") (pin "J3") (pinfunction "DQL6_J3") (pintype "passive"))
    )
    (net (code "55") (name "DDR4_DQL6_B") (class "Default")
      (node (ref "U3301") (pin "J3") (pinfunction "DQL6_J3") (pintype "passive"))
    )
    (net (code "56") (name "DDR4_DQL7_A") (class "Default")
      (node (ref "U3300") (pin "J7") (pinfunction "DQL7_J7") (pintype "passive"))
    )
    (net (code "57") (name "DDR4_DQL7_B") (class "Default")
      (node (ref "U3301") (pin "J7") (pinfunction "DQL7_J7") (pintype "passive"))
    )
    (net (code "58") (name "DDR4_DQSL_N_A") (class "Default")
      (node (ref "U3300") (pin "F3") (pinfunction "DQSL_N_F3") (pintype "passive"))
    )
    (net (code "59") (name "DDR4_DQSL_N_B") (class "Default")
      (node (ref "U3301") (pin "F3") (pinfunction "DQSL_N_F3") (pintype "passive"))
    )
    (net (code "60") (name "DDR4_DQSL_P_A") (class "Default")
      (node (ref "U3300") (pin "G3") (pinfunction "DQSL_P_G3") (pintype "passive"))
    )
    (net (code "61") (name "DDR4_DQSL_P_B") (class "Default")
      (node (ref "U3301") (pin "G3") (pinfunction "DQSL_P_G3") (pintype "passive"))
    )
    (net (code "62") (name "DDR4_DQSU_N_A") (class "Default")
      (node (ref "U3300") (pin "A7") (pinfunction "DQSU_N_A7") (pintype "passive"))
    )
    (net (code "63") (name "DDR4_DQSU_N_B") (class "Default")
      (node (ref "U3301") (pin "A7") (pinfunction "DQSU_N_A7") (pintype "passive"))
    )
    (net (code "64") (name "DDR4_DQSU_P_A") (class "Default")
      (node (ref "U3300") (pin "B7") (pinfunction "DQSU_P_B7") (pintype "passive"))
    )
    (net (code "65") (name "DDR4_DQSU_P_B") (class "Default")
      (node (ref "U3301") (pin "B7") (pinfunction "DQSU_P_B7") (pintype "passive"))
    )
    (net (code "66") (name "DDR4_DQU0_A") (class "Default")
      (node (ref "U3300") (pin "A3") (pinfunction "DQU0_A3") (pintype "passive"))
    )
    (net (code "67") (name "DDR4_DQU0_B") (class "Default")
      (node (ref "U3301") (pin "A3") (pinfunction "DQU0_A3") (pintype "passive"))
    )
    (net (code "68") (name "DDR4_DQU1_A") (class "Default")
      (node (ref "U3300") (pin "B8") (pinfunction "DQU1_B8") (pintype "passive"))
    )
    (net (code "69") (name "DDR4_DQU1_B") (class "Default")
      (node (ref "U3301") (pin "B8") (pinfunction "DQU1_B8") (pintype "passive"))
    )
    (net (code "70") (name "DDR4_DQU2_A") (class "Default")
      (node (ref "U3300") (pin "C3") (pinfunction "DQU2_C3") (pintype "passive"))
    )
    (net (code "71") (name "DDR4_DQU2_B") (class "Default")
      (node (ref "U3301") (pin "C3") (pinfunction "DQU2_C3") (pintype "passive"))
    )
    (net (code "72") (name "DDR4_DQU3_A") (class "Default")
      (node (ref "U3300") (pin "C7") (pinfunction "DQU3_C7") (pintype "passive"))
    )
    (net (code "73") (name "DDR4_DQU3_B") (class "Default")
      (node (ref "U3301") (pin "C7") (pinfunction "DQU3_C7") (pintype "passive"))
    )
    (net (code "74") (name "DDR4_DQU4_A") (class "Default")
      (node (ref "U3300") (pin "C2") (pinfunction "DQU4_C2") (pintype "passive"))
    )
    (net (code "75") (name "DDR4_DQU4_B") (class "Default")
      (node (ref "U3301") (pin "C2") (pinfunction "DQU4_C2") (pintype "passive"))
    )
    (net (code "76") (name "DDR4_DQU5_A") (class "Default")
      (node (ref "U3300") (pin "C8") (pinfunction "DQU5_C8") (pintype "passive"))
    )
    (net (code "77") (name "DDR4_DQU5_B") (class "Default")
      (node (ref "U3301") (pin "C8") (pinfunction "DQU5_C8") (pintype "passive"))
    )
    (net (code "78") (name "DDR4_DQU6_A") (class "Default")
      (node (ref "U3300") (pin "D3") (pinfunction "DQU6_D3") (pintype "passive"))
    )
    (net (code "79") (name "DDR4_DQU6_B") (class "Default")
      (node (ref "U3301") (pin "D3") (pinfunction "DQU6_D3") (pintype "passive"))
    )
    (net (code "80") (name "DDR4_DQU7_A") (class "Default")
      (node (ref "U3300") (pin "D7") (pinfunction "DQU7_D7") (pintype "passive"))
    )
    (net (code "81") (name "DDR4_DQU7_B") (class "Default")
      (node (ref "U3301") (pin "D7") (pinfunction "DQU7_D7") (pintype "passive"))
    )
    (net (code "82") (name "DDR4_ODT0") (class "Default")
      (node (ref "R3310") (pin "2") (pinfunction "2_2") (pintype "passive"))
      (node (ref "R3311") (pin "1") (pinfunction "1_1") (pintype "passive"))
    )
    (net (code "83") (name "DDR4_RESETn") (class "Default")
      (node (ref "C3301") (pin "1") (pinfunction "1_1") (pintype "passive"))
      (node (ref "C3302") (pin "1") (pinfunction "1_1") (pintype "passive"))
      (node (ref "U3300") (pin "P1") (pinfunction "RESET_n_P1") (pintype "passive"))
      (node (ref "U3301") (pin "P1") (pinfunction "RESET_n_P1") (pintype "passive"))
    )
    (net (code "84") (name "DDRPHY_VREFOUT") (class "Default")
      (node (ref "C3303") (pin "2") (pinfunction "2_2") (pintype "passive"))
      (node (ref "C3304") (pin "1") (pinfunction "1_1") (pintype "passive"))
      (node (ref "R3322") (pin "2") (pinfunction "2_2") (pintype "passive"))
    )
    (net (code "85") (name "GND") (class "Default")
      (node (ref "C3300") (pin "2") (pinfunction "2_2") (pintype "passive"))
      (node (ref "C3301") (pin "2") (pinfunction "2_2") (pintype "passive"))
      (node (ref "C3302") (pin "2") (pinfunction "2_2") (pintype "passive"))
      (node (ref "C3304") (pin "2") (pinfunction "2_2") (pintype "passive"))
      (node (ref "C3305") (pin "2") (pinfunction "2_2") (pintype "passive"))
      (node (ref "C3306") (pin "2") (pinfunction "2_2") (pintype "passive"))
      (node (ref "C3307") (pin "2") (pinfunction "2_2") (pintype "passive"))
      (node (ref "C3308") (pin "2") (pinfunction "2_2") (pintype "passive"))
      (node (ref "C3309") (pin "2") (pinfunction "2_2") (pintype "passive"))
      (node (ref "C3310") (pin "2") (pinfunction "2_2") (pintype "passive"))
      (node (ref "C3311") (pin "2") (pinfunction "2_2") (pintype "passive"))
      (node (ref "C3312") (pin "2") (pinfunction "2_2") (pintype "passive"))
      (node (ref "C3313") (pin "2") (pinfunction "2_2") (pintype "passive"))
      (node (ref "C3314") (pin "2") (pinfunction "2_2") (pintype "passive"))
      (node (ref "C3315") (pin "2") (pinfunction "2_2") (pintype "passive"))
      (node (ref "C3316") (pin "2") (pinfunction "2_2") (pintype "passive"))
      (node (ref "C3317") (pin "2") (pinfunction "2_2") (pintype "passive"))
      (node (ref "C3318") (pin "2") (pinfunction "2_2") (pintype "passive"))
      (node (ref "C3319") (pin "2") (pinfunction "2_2") (pintype "passive"))
      (node (ref "C3320") (pin "2") (pinfunction "2_2") (pintype "passive"))
      (node (ref "C3321") (pin "2") (pinfunction "2_2") (pintype "passive"))
      (node (ref "C3322") (pin "2") (pinfunction "2_2") (pintype "passive"))
      (node (ref "C3323") (pin "2") (pinfunction "2_2") (pintype "passive"))
      (node (ref "C3325") (pin "2") (pinfunction "2_2") (pintype "passive"))
      (node (ref "C3326") (pin "2") (pinfunction "2_2") (pintype "passive"))
      (node (ref "C3327") (pin "2") (pinfunction "2_2") (pintype "passive"))
      (node (ref "C3328") (pin "2") (pinfunction "2_2") (pintype "passive"))
      (node (ref "C3329") (pin "2") (pinfunction "2_2") (pintype "passive"))
      (node (ref "C3330") (pin "2") (pinfunction "2_2") (pintype "passive"))
      (node (ref "C3331") (pin "2") (pinfunction "2_2") (pintype "passive"))
      (node (ref "C3332") (pin "2") (pinfunction "2_2") (pintype "passive"))
      (node (ref "C3333") (pin "2") (pinfunction "2_2") (pintype "passive"))
      (node (ref "C3334") (pin "2") (pinfunction "2_2") (pintype "passive"))
      (node (ref "C3335") (pin "2") (pinfunction "2_2") (pintype "passive"))
      (node (ref "C3336") (pin "2") (pinfunction "2_2") (pintype "passive"))
      (node (ref "C3337") (pin "2") (pinfunction "2_2") (pintype "passive"))
      (node (ref "C3338") (pin "2") (pinfunction "2_2") (pintype "passive"))
      (node (ref "C3339") (pin "2") (pinfunction "2_2") (pintype "passive"))
      (node (ref "C3340") (pin "2") (pinfunction "2_2") (pintype "passive"))
      (node (ref "C3341") (pin "2") (pinfunction "2_2") (pintype "passive"))
      (node (ref "C3342") (pin "2") (pinfunction "2_2") (pintype "passive"))
      (node (ref "C3343") (pin "2") (pinfunction "2_2") (pintype "passive"))
      (node (ref "C3344") (pin "2") (pinfunction "2_2") (pintype "passive"))
      (node (ref "C3345") (pin "2") (pinfunction "2_2") (pintype "passive"))
      (node (ref "R3312") (pin "2") (pinfunction "2_2") (pintype "passive"))
      (node (ref "R3313") (pin "2") (pinfunction "2_2") (pintype "passive"))
      (node (ref "R3314") (pin "2") (pinfunction "2_2") (pintype "passive"))
      (node (ref "R3315") (pin "2") (pinfunction "2_2") (pintype "passive"))
      (node (ref "R3316") (pin "2") (pinfunction "2_2") (pintype "passive"))
      (node (ref "R3317") (pin "2") (pinfunction "2_2") (pintype "passive"))
      (node (ref "R3318") (pin "2") (pinfunction "2_2") (pintype "passive"))
      (node (ref "R3319") (pin "2") (pinfunction "2_2") (pintype "passive"))
      (node (ref "R3323") (pin "2") (pinfunction "2_2") (pintype "passive"))
      (node (ref "U3300") (pin "A2") (pinfunction "VSSQ_A2") (pintype "power_in"))
      (node (ref "U3300") (pin "A8") (pinfunction "VSSQ_A8") (pintype "power_in"))
      (node (ref "U3300") (pin "B2") (pinfunction "VSS_B2") (pintype "power_in"))
      (node (ref "U3300") (pin "C9") (pinfunction "VSSQ_C9") (pintype "power_in"))
      (node (ref "U3300") (pin "D2") (pinfunction "VSSQ_D2") (pintype "power_in"))
      (node (ref "U3300") (pin "D8") (pinfunction "VSSQ_D8") (pintype "power_in"))
      (node (ref "U3300") (pin "E1") (pinfunction "VSS_E1") (pintype "power_in"))
      (node (ref "U3300") (pin "E3") (pinfunction "VSSQ_E3") (pintype "power_in"))
      (node (ref "U3300") (pin "E8") (pinfunction "VSSQ_E8") (pintype "power_in"))
      (node (ref "U3300") (pin "F1") (pinfunction "VSSQ_F1") (pintype "power_in"))
      (node (ref "U3300") (pin "G8") (pinfunction "VSS_G8") (pintype "power_in"))
      (node (ref "U3300") (pin "H1") (pinfunction "VSSQ_H1") (pintype "power_in"))
      (node (ref "U3300") (pin "H9") (pinfunction "VSSQ_H9") (pintype "power_in"))
      (node (ref "U3300") (pin "K1") (pinfunction "VSS_K1") (pintype "power_in"))
      (node (ref "U3300") (pin "K9") (pinfunction "VSS_K9") (pintype "power_in"))
      (node (ref "U3300") (pin "N1") (pinfunction "VSS_N1") (pintype "power_in"))
      (node (ref "U3300") (pin "N9") (pinfunction "TEN_N9") (pintype "passive"))
      (node (ref "U3300") (pin "T1") (pinfunction "VSS_T1") (pintype "power_in"))
      (node (ref "U3300") (pin "T3") (pinfunction "PAR_T3") (pintype "passive"))
      (node (ref "U3301") (pin "A2") (pinfunction "VSSQ_A2") (pintype "power_in"))
      (node (ref "U3301") (pin "A8") (pinfunction "VSSQ_A8") (pintype "power_in"))
      (node (ref "U3301") (pin "B2") (pinfunction "VSS_B2") (pintype "power_in"))
      (node (ref "U3301") (pin "C9") (pinfunction "VSSQ_C9") (pintype "power_in"))
      (node (ref "U3301") (pin "D2") (pinfunction "VSSQ_D2") (pintype "power_in"))
      (node (ref "U3301") (pin "D8") (pinfunction "VSSQ_D8") (pintype "power_in"))
      (node (ref "U3301") (pin "E1") (pinfunction "VSS_E1") (pintype "power_in"))
      (node (ref "U3301") (pin "E3") (pinfunction "VSSQ_E3") (pintype "power_in"))
      (node (ref "U3301") (pin "E8") (pinfunction "VSSQ_E8") (pintype "power_in"))
      (node (ref "U3301") (pin "F1") (pinfunction "VSSQ_F1") (pintype "power_in"))
      (node (ref "U3301") (pin "G8") (pinfunction "VSS_G8") (pintype "power_in"))
      (node (ref "U3301") (pin "H1") (pinfunction "VSSQ_H1") (pintype "power_in"))
      (node (ref "U3301") (pin "H9") (pinfunction "VSSQ_H9") (pintype "power_in"))
      (node (ref "U3301") (pin "K1") (pinfunction "VSS_K1") (pintype "power_in"))
      (node (ref "U3301") (pin "K9") (pinfunction "VSS_K9") (pintype "power_in"))
      (node (ref "U3301") (pin "N1") (pinfunction "VSS_N1") (pintype "power_in"))
      (node (ref "U3301") (pin "N9") (pinfunction "TEN_N9") (pintype "passive"))
      (node (ref "U3301") (pin "T1") (pinfunction "VSS_T1") (pintype "power_in"))
      (node (ref "U3301") (pin "T3") (pinfunction "PAR_T3") (pintype "passive"))
      (node (ref "U3302") (pin "2") (pinfunction "GND_2") (pintype "passive"))
    )
    (net (code "86") (name "Net-(C3300-Pad1)") (class "Default")
      (node (ref "C3300") (pin "1") (pinfunction "1_1") (pintype "passive"))
      (node (ref "R3300") (pin "2") (pinfunction "2_2") (pintype "passive"))
      (node (ref "R3301") (pin "2") (pinfunction "2_2") (pintype "passive"))
    )
    (net (code "87") (name "Net-(R3316-Pad1)") (class "Default")
      (node (ref "R3316") (pin "1") (pinfunction "1_1") (pintype "passive"))
      (node (ref "U3301") (pin "E9") (pinfunction "VSS_E9") (pintype "power_in"))
    )
    (net (code "88") (name "Net-(R3317-Pad1)") (class "Default")
      (node (ref "R3317") (pin "1") (pinfunction "1_1") (pintype "passive"))
      (node (ref "U3300") (pin "E9") (pinfunction "VSS_E9") (pintype "power_in"))
    )
    (net (code "89") (name "Net-(U3300-NC)") (class "Default")
      (node (ref "R3315") (pin "1") (pinfunction "1_1") (pintype "passive"))
      (node (ref "U3300") (pin "T7") (pinfunction "NC_T7") (pintype "passive"))
    )
    (net (code "90") (name "Net-(U3300-ZQ)") (class "Default")
      (node (ref "R3313") (pin "1") (pinfunction "1_1") (pintype "passive"))
      (node (ref "U3300") (pin "F9") (pinfunction "ZQ_F9") (pintype "passive"))
    )
    (net (code "91") (name "Net-(U3301-NC)") (class "Default")
      (node (ref "R3314") (pin "1") (pinfunction "1_1") (pintype "passive"))
      (node (ref "U3301") (pin "T7") (pinfunction "NC_T7") (pintype "passive"))
    )
    (net (code "92") (name "Net-(U3301-ZQ)") (class "Default")
      (node (ref "R3312") (pin "1") (pinfunction "1_1") (pintype "passive"))
      (node (ref "U3301") (pin "F9") (pinfunction "ZQ_F9") (pintype "passive"))
    )
    (net (code "93") (name "Net-(U3302-BP)") (class "Default")
      (node (ref "C3330") (pin "1") (pinfunction "1_1") (pintype "passive"))
      (node (ref "U3302") (pin "4") (pinfunction "BP_4") (pintype "passive"))
    )
    (net (code "94") (name "Net-(U3302-EN)") (class "Default")
      (node (ref "C3329") (pin "1") (pinfunction "1_1") (pintype "passive"))
      (node (ref "R3325") (pin "2") (pinfunction "2_2") (pintype "passive"))
      (node (ref "U3302") (pin "3") (pinfunction "EN_3") (pintype "passive"))
    )
    (net (code "95") (name "VCC3V3_SYS") (class "Default")
      (node (ref "C3322") (pin "1") (pinfunction "1_1") (pintype "passive"))
      (node (ref "R3325") (pin "1") (pinfunction "1_1") (pintype "passive"))
      (node (ref "U3302") (pin "1") (pinfunction "IN_1") (pintype "passive"))
    )
    (net (code "96") (name "VCC25_DDR") (class "Default")
      (node (ref "C3323") (pin "1") (pinfunction "1_1") (pintype "passive"))
      (node (ref "C3325") (pin "1") (pinfunction "1_1") (pintype "passive"))
      (node (ref "C3326") (pin "1") (pinfunction "1_1") (pintype "passive"))
      (node (ref "C3327") (pin "1") (pinfunction "1_1") (pintype "passive"))
      (node (ref "C3328") (pin "1") (pinfunction "1_1") (pintype "passive"))
      (node (ref "U3300") (pin "B1") (pinfunction "VPP1_B1") (pintype "passive"))
      (node (ref "U3300") (pin "R9") (pinfunction "VPP2_R9") (pintype "passive"))
      (node (ref "U3301") (pin "B1") (pinfunction "VPP1_B1") (pintype "passive"))
      (node (ref "U3301") (pin "R9") (pinfunction "VPP2_R9") (pintype "passive"))
      (node (ref "U3302") (pin "5") (pinfunction "OUT_5") (pintype "passive"))
    )
    (net (code "97") (name "VCC_DDR") (class "Default")
      (node (ref "C3303") (pin "1") (pinfunction "1_1") (pintype "passive"))
      (node (ref "C3307") (pin "1") (pinfunction "1_1") (pintype "passive"))
      (node (ref "C3308") (pin "1") (pinfunction "1_1") (pintype "passive"))
      (node (ref "C3309") (pin "1") (pinfunction "1_1") (pintype "passive"))
      (node (ref "C3310") (pin "1") (pinfunction "1_1") (pintype "passive"))
      (node (ref "C3311") (pin "1") (pinfunction "1_1") (pintype "passive"))
      (node (ref "C3312") (pin "1") (pinfunction "1_1") (pintype "passive"))
      (node (ref "C3313") (pin "1") (pinfunction "1_1") (pintype "passive"))
      (node (ref "C3314") (pin "1") (pinfunction "1_1") (pintype "passive"))
      (node (ref "C3315") (pin "1") (pinfunction "1_1") (pintype "passive"))
      (node (ref "C3316") (pin "1") (pinfunction "1_1") (pintype "passive"))
      (node (ref "C3317") (pin "1") (pinfunction "1_1") (pintype "passive"))
      (node (ref "C3318") (pin "1") (pinfunction "1_1") (pintype "passive"))
      (node (ref "C3319") (pin "1") (pinfunction "1_1") (pintype "passive"))
      (node (ref "C3320") (pin "1") (pinfunction "1_1") (pintype "passive"))
      (node (ref "C3321") (pin "1") (pinfunction "1_1") (pintype "passive"))
      (node (ref "C3331") (pin "1") (pinfunction "1_1") (pintype "passive"))
      (node (ref "C3332") (pin "1") (pinfunction "1_1") (pintype "passive"))
      (node (ref "C3333") (pin "1") (pinfunction "1_1") (pintype "passive"))
      (node (ref "C3334") (pin "1") (pinfunction "1_1") (pintype "passive"))
      (node (ref "C3335") (pin "1") (pinfunction "1_1") (pintype "passive"))
      (node (ref "C3336") (pin "1") (pinfunction "1_1") (pintype "passive"))
      (node (ref "C3337") (pin "1") (pinfunction "1_1") (pintype "passive"))
      (node (ref "C3338") (pin "1") (pinfunction "1_1") (pintype "passive"))
      (node (ref "C3339") (pin "1") (pinfunction "1_1") (pintype "passive"))
      (node (ref "C3340") (pin "1") (pinfunction "1_1") (pintype "passive"))
      (node (ref "C3341") (pin "1") (pinfunction "1_1") (pintype "passive"))
      (node (ref "C3342") (pin "1") (pinfunction "1_1") (pintype "passive"))
      (node (ref "C3343") (pin "1") (pinfunction "1_1") (pintype "passive"))
      (node (ref "C3344") (pin "1") (pinfunction "1_1") (pintype "passive"))
      (node (ref "C3345") (pin "1") (pinfunction "1_1") (pintype "passive"))
      (node (ref "R3321") (pin "1") (pinfunction "1_1") (pintype "passive"))
      (node (ref "U3300") (pin "A1") (pinfunction "VDDQ_A1") (pintype "power_in"))
      (node (ref "U3300") (pin "A9") (pinfunction "VDDQ_A9") (pintype "power_in"))
      (node (ref "U3300") (pin "B3") (pinfunction "VDD_B3") (pintype "power_in"))
      (node (ref "U3300") (pin "B9") (pinfunction "VDD_B9") (pintype "power_in"))
      (node (ref "U3300") (pin "C1") (pinfunction "VDDQ_C1") (pintype "power_in"))
      (node (ref "U3300") (pin "D1") (pinfunction "VDD_D1") (pintype "power_in"))
      (node (ref "U3300") (pin "D9") (pinfunction "VDDQ_D9") (pintype "power_in"))
      (node (ref "U3300") (pin "F2") (pinfunction "VDDQ_F2") (pintype "power_in"))
      (node (ref "U3300") (pin "F8") (pinfunction "VDDQ_F8") (pintype "power_in"))
      (node (ref "U3300") (pin "G1") (pinfunction "VDDQ_G1") (pintype "power_in"))
      (node (ref "U3300") (pin "G7") (pinfunction "VDD_G7") (pintype "power_in"))
      (node (ref "U3300") (pin "G9") (pinfunction "VDDQ_G9") (pintype "power_in"))
      (node (ref "U3300") (pin "J1") (pinfunction "VDD_J1") (pintype "power_in"))
      (node (ref "U3300") (pin "J2") (pinfunction "VDDQ_J2") (pintype "power_in"))
      (node (ref "U3300") (pin "J8") (pinfunction "VDDQ_J8") (pintype "power_in"))
      (node (ref "U3300") (pin "J9") (pinfunction "VDD_J9") (pintype "power_in"))
      (node (ref "U3300") (pin "L1") (pinfunction "VDD_L1") (pintype "power_in"))
      (node (ref "U3300") (pin "L9") (pinfunction "VDD_L9") (pintype "power_in"))
      (node (ref "U3300") (pin "R1") (pinfunction "VDD_R1") (pintype "power_in"))
      (node (ref "U3300") (pin "T9") (pinfunction "VDD_T9") (pintype "power_in"))
      (node (ref "U3301") (pin "A1") (pinfunction "VDDQ_A1") (pintype "power_in"))
      (node (ref "U3301") (pin "A9") (pinfunction "VDDQ_A9") (pintype "power_in"))
      (node (ref "U3301") (pin "B3") (pinfunction "VDD_B3") (pintype "power_in"))
      (node (ref "U3301") (pin "B9") (pinfunction "VDD_B9") (pintype "power_in"))
      (node (ref "U3301") (pin "C1") (pinfunction "VDDQ_C1") (pintype "power_in"))
      (node (ref "U3301") (pin "D1") (pinfunction "VDD_D1") (pintype "power_in"))
      (node (ref "U3301") (pin "D9") (pinfunction "VDDQ_D9") (pintype "power_in"))
      (node (ref "U3301") (pin "F2") (pinfunction "VDDQ_F2") (pintype "power_in"))
      (node (ref "U3301") (pin "F8") (pinfunction "VDDQ_F8") (pintype "power_in"))
      (node (ref "U3301") (pin "G1") (pinfunction "VDDQ_G1") (pintype "power_in"))
      (node (ref "U3301") (pin "G7") (pinfunction "VDD_G7") (pintype "power_in"))
      (node (ref "U3301") (pin "G9") (pinfunction "VDDQ_G9") (pintype "power_in"))
      (node (ref "U3301") (pin "J1") (pinfunction "VDD_J1") (pintype "power_in"))
      (node (ref "U3301") (pin "J2") (pinfunction "VDDQ_J2") (pintype "power_in"))
      (node (ref "U3301") (pin "J8") (pinfunction "VDDQ_J8") (pintype "power_in"))
      (node (ref "U3301") (pin "J9") (pinfunction "VDD_J9") (pintype "power_in"))
      (node (ref "U3301") (pin "L1") (pinfunction "VDD_L1") (pintype "power_in"))
      (node (ref "U3301") (pin "L9") (pinfunction "VDD_L9") (pintype "power_in"))
      (node (ref "U3301") (pin "R1") (pinfunction "VDD_R1") (pintype "power_in"))
      (node (ref "U3301") (pin "T9") (pinfunction "VDD_T9") (pintype "power_in"))
    )
    (net (code "98") (name "VREF_DDR4_CA") (class "Default")
      (node (ref "C3305") (pin "1") (pinfunction "1_1") (pintype "passive"))
      (node (ref "C3306") (pin "1") (pinfunction "1_1") (pintype "passive"))
      (node (ref "R3321") (pin "2") (pinfunction "2_2") (pintype "passive"))
      (node (ref "R3322") (pin "1") (pinfunction "1_1") (pintype "passive"))
      (node (ref "R3323") (pin "1") (pinfunction "1_1") (pintype "passive"))
      (node (ref "U3300") (pin "M1") (pinfunction "VREFCA_M1") (pintype "passive"))
      (node (ref "U3301") (pin "M1") (pinfunction "VREFCA_M1") (pintype "passive"))
    )
    (net (code "99") (name "unconnected-(U3300-ALERT_n-PadP9)") (class "Default")
      (node (ref "U3300") (pin "P9") (pinfunction "ALERT_n_P9") (pintype "passive"))
    )
    (net (code "100") (name "unconnected-(U3301-ALERT_n-PadP9)") (class "Default")
      (node (ref "U3301") (pin "P9") (pinfunction "ALERT_n_P9") (pintype "passive"))
    )
  )
)
